# key.net
KiCad netlist of a schematic drawn in Altium Designer
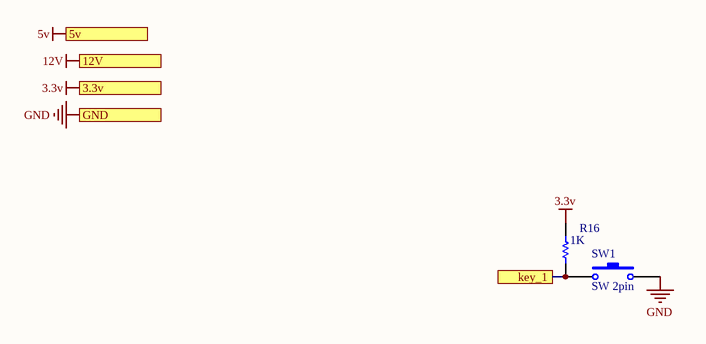
[diagram p0: key.SchDoc]

(export (version "E")
  (design (tool "Eeschema 10.0.6"))
  (components
    (comp (ref "R16")
      (value "1K")
      (footprint "RES 0805 optional")
      (fields (field (name "Comment") "resistor"))
      (libsource (lib "m_faryabi") (part "resistor"))
    )
    (comp (ref "SW1") (value "SW 2pin") (footprint "SW 2PIN") (libsource (lib "m_faryabi") (part "SW 2pin")))
  )
  (nets
    (net (code "1") (name "/key_1") (class "Default")
      (node (ref "R16") (pin "1") (pinfunction "1_1") (pintype "passive"))
      (node (ref "SW1") (pin "1") (pinfunction "1_1") (pintype "passive"))
    )
    (net (code "2") (name "3.3v") (class "Default")
      (node (ref "R16") (pin "2") (pinfunction "2_2") (pintype "passive"))
    )
    (net (code "5") (name "GND") (class "Default")
      (node (ref "SW1") (pin "2") (pinfunction "2_2") (pintype "passive"))
    )
  )
)
